# k210_V3_0.net
KiCad netlist of a schematic drawn in Altium Designer
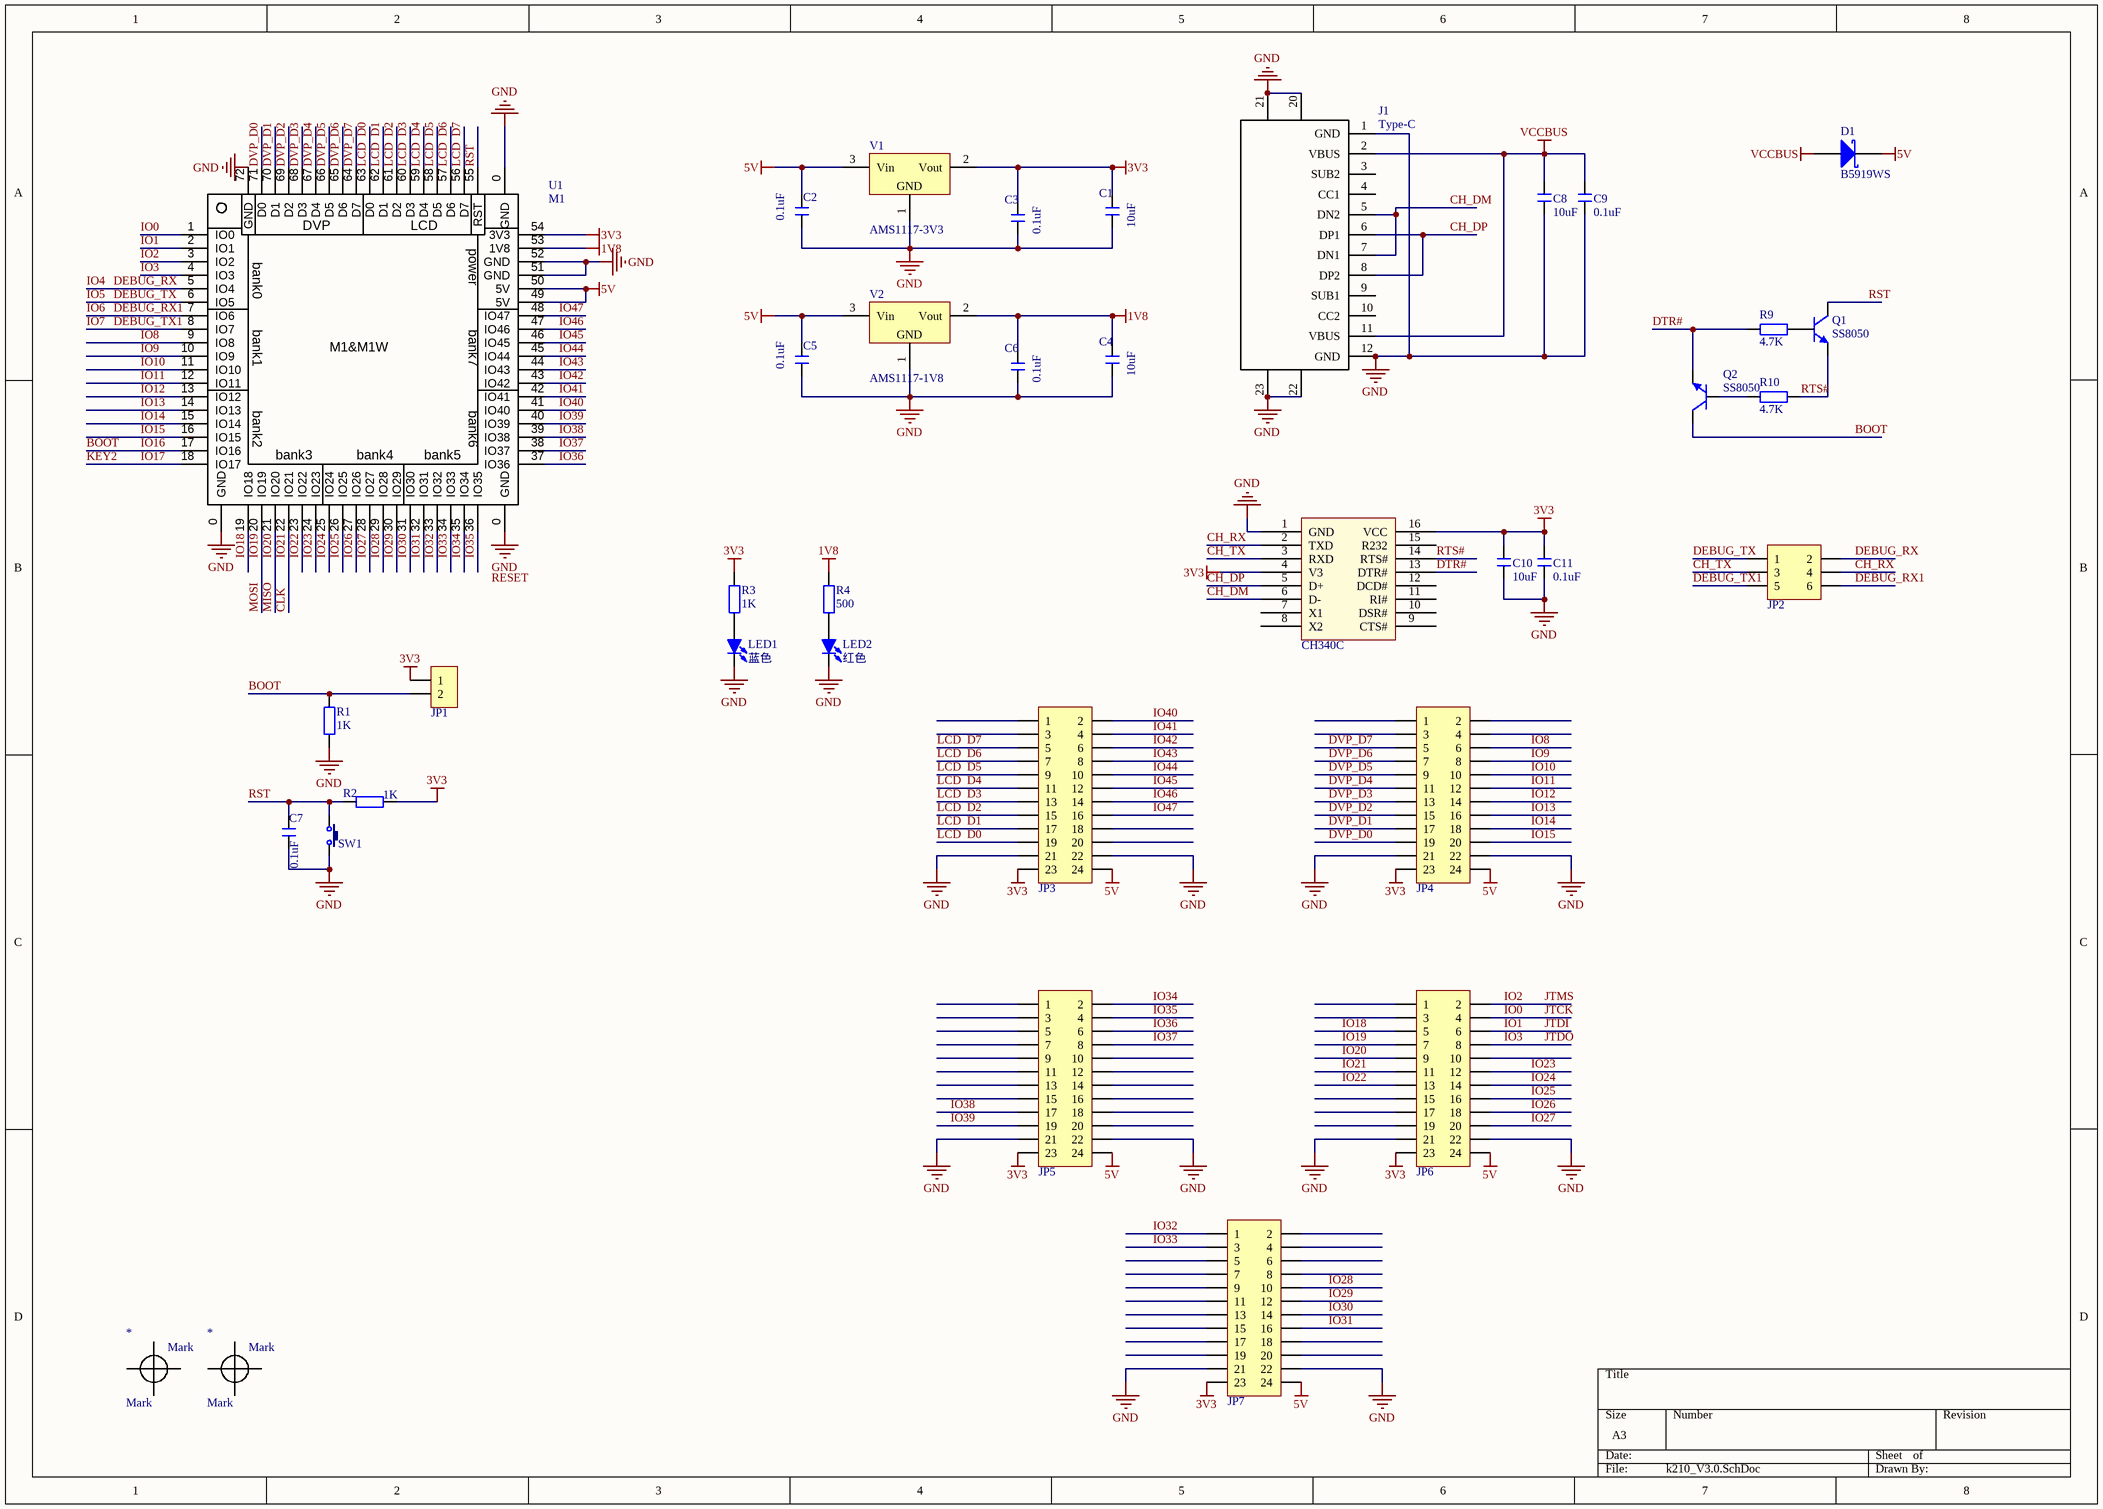
[diagram p0: k210_V3.0.SchDoc]

(export (version "E")
  (design (tool "Eeschema 10.0.6"))
  (components
    (comp (ref "C1")
      (value "10uF")
      (footprint "C 0603_L")
      (description "贴片电容")
      (libsource (lib "0.1 - 电阻-电容-电感") (part "C"))
    )
    (comp (ref "C2")
      (value "0.1uF")
      (footprint "C 0603_L")
      (description "贴片电容")
      (libsource (lib "0.1 - 电阻-电容-电感") (part "C"))
    )
    (comp (ref "C3")
      (value "0.1uF")
      (footprint "C 0603_L")
      (description "贴片电容")
      (libsource (lib "0.1 - 电阻-电容-电感") (part "C"))
    )
    (comp (ref "C4")
      (value "10uF")
      (footprint "C 0603_L")
      (description "贴片电容")
      (libsource (lib "0.1 - 电阻-电容-电感") (part "C"))
    )
    (comp (ref "C5")
      (value "0.1uF")
      (footprint "C 0603_L")
      (description "贴片电容")
      (libsource (lib "0.1 - 电阻-电容-电感") (part "C"))
    )
    (comp (ref "C6")
      (value "0.1uF")
      (footprint "C 0603_L")
      (description "贴片电容")
      (libsource (lib "0.1 - 电阻-电容-电感") (part "C"))
    )
    (comp (ref "C7")
      (value "0.1uF")
      (footprint "C 0603_L")
      (description "贴片电容")
      (libsource (lib "0.1 - 电阻-电容-电感") (part "C"))
    )
    (comp (ref "C8")
      (value "10uF")
      (footprint "C 0603_L")
      (description "贴片电容")
      (libsource (lib "0.1 - 电阻-电容-电感") (part "C"))
    )
    (comp (ref "C9")
      (value "0.1uF")
      (footprint "C 0603_L")
      (description "贴片电容")
      (libsource (lib "0.1 - 电阻-电容-电感") (part "C"))
    )
    (comp (ref "C10")
      (value "10uF")
      (footprint "C 0603_L")
      (description "贴片电容")
      (libsource (lib "0.1 - 电阻-电容-电感") (part "C"))
    )
    (comp (ref "C11")
      (value "0.1uF")
      (footprint "C 0603_L")
      (description "贴片电容")
      (libsource (lib "0.1 - 电阻-电容-电感") (part "C"))
    )
    (comp (ref "CH340C")
      (value "CH340G")
      (footprint "sop16_L")
      (libsource (lib "1.9 - CH340系列编程器芯片") (part "CH340G"))
    )
    (comp (ref "D1")
      (value "B5919WS")
      (footprint "SOD-323")
      (description "肖特基二极管")
      (libsource (lib "0.2 - 二极管-整流桥") (part "1N5819"))
    )
    (comp (ref "J1")
      (value "Type-C")
      (footprint "Type-C-16")
      (libsource (lib "TYPE-C-16PIN") (part "Type-C"))
    )
    (comp (ref "JP1")
      (value "HDR-1X2")
      (footprint "HDR2.54-M-LI-2P")
      (description "2P接插件")
      (fields (field (name "版权归属") "封装库来自淘宝 ID：黄晶宝石"))
      (libsource (lib "5.4 - 接插件-脚距2.54 (100mil) ") (part "Header 2"))
    )
    (comp (ref "JP2")
      (value "Header3X2")
      (footprint "HDR2.54-LI-2x3P")
      (description "3*2P接插件")
      (fields (field (name "版权归属") "封装库来自淘宝 ID：黄晶宝石"))
      (libsource (lib "5.4 - 接插件-脚距2.54 (100mil) ") (part "Header 3X2"))
    )
    (comp (ref "JP3")
      (value "Header 2X11")
      (footprint "HDR2.54-WI-2x12P")
      (description "12*2P接插件")
      (fields (field (name "版权归属") "封装库来自淘宝卖家 ID：黄晶宝石"))
      (libsource (lib "5.4 - 接插件-脚距2.54 (100mil) ") (part "Header 12X2"))
    )
    (comp (ref "JP4")
      (value "Header 2X11")
      (footprint "HDR2.54-WI-2x12P")
      (description "12*2P接插件")
      (fields (field (name "版权归属") "封装库来自淘宝卖家 ID：黄晶宝石"))
      (libsource (lib "5.4 - 接插件-脚距2.54 (100mil) ") (part "Header 12X2"))
    )
    (comp (ref "JP5")
      (value "Header 2X11")
      (footprint "HDR2.54-WI-2x12P")
      (description "12*2P接插件")
      (fields (field (name "版权归属") "封装库来自淘宝卖家 ID：黄晶宝石"))
      (libsource (lib "5.4 - 接插件-脚距2.54 (100mil) ") (part "Header 12X2"))
    )
    (comp (ref "JP6")
      (value "Header 2X11")
      (footprint "HDR2.54-WI-2x12P")
      (description "12*2P接插件")
      (fields (field (name "版权归属") "封装库来自淘宝卖家 ID：黄晶宝石"))
      (libsource (lib "5.4 - 接插件-脚距2.54 (100mil) ") (part "Header 12X2"))
    )
    (comp (ref "JP7")
      (value "Header 2X11")
      (footprint "HDR2.54-WI-2x12P")
      (description "12*2P接插件")
      (fields (field (name "版权归属") "封装库来自淘宝卖家 ID：黄晶宝石"))
      (libsource (lib "5.4 - 接插件-脚距2.54 (100mil) ") (part "Header 12X2"))
    )
    (comp (ref "LED1")
      (value "蓝色")
      (footprint "LED 0603R")
      (description "贴片LED")
      (fields (field (name "版权归属") "封装库来自淘宝 ID：黄晶宝石"))
      (libsource (lib "0.3 - LED发光二极管") (part "LED-SMD"))
    )
    (comp (ref "LED2")
      (value "红色")
      (footprint "LED 0603R")
      (description "贴片LED")
      (fields (field (name "版权归属") "封装库来自淘宝 ID：黄晶宝石"))
      (libsource (lib "0.3 - LED发光二极管") (part "LED-SMD"))
    )
    (comp (ref "Q1")
      (value "SS8050")
      (footprint "SOT23-3N")
      (description "高频放大-NPN型")
      (fields (field (name "版权归属") "封装库来自淘宝 ID：黄晶宝石"))
      (libsource (lib "0.4 - 三极管") (part "8050-SMD"))
    )
    (comp (ref "Q2")
      (value "SS8050")
      (footprint "SOT23-3N")
      (description "高频放大-NPN型")
      (fields (field (name "版权归属") "封装库来自淘宝 ID：黄晶宝石"))
      (libsource (lib "0.4 - 三极管") (part "8050-SMD"))
    )
    (comp (ref "R1")
      (value "1K")
      (footprint "R 0603_L")
      (description "贴片电阻")
      (libsource (lib "0.1 - 电阻-电容-电感") (part "R"))
    )
    (comp (ref "R2")
      (value "1K")
      (footprint "R 0603_L")
      (description "贴片电阻")
      (libsource (lib "0.1 - 电阻-电容-电感") (part "R"))
    )
    (comp (ref "R3")
      (value "1K")
      (footprint "R 0603_L")
      (description "贴片电阻")
      (fields (field (name "版权归属") "来自淘宝 ID：黄晶宝石"))
      (libsource (lib "0.1 - 电阻-电容-电感") (part "R"))
    )
    (comp (ref "R4")
      (value "500")
      (footprint "R 0603_L")
      (description "贴片电阻")
      (fields (field (name "版权归属") "来自淘宝 ID：黄晶宝石"))
      (libsource (lib "0.1 - 电阻-电容-电感") (part "R"))
    )
    (comp (ref "R9")
      (value "4.7K")
      (footprint "R 0603_L")
      (description "贴片电阻")
      (fields (field (name "版权归属") "来自淘宝 ID：黄晶宝石"))
      (libsource (lib "0.1 - 电阻-电容-电感") (part "R"))
    )
    (comp (ref "R10")
      (value "4.7K")
      (footprint "R 0603_L")
      (description "贴片电阻")
      (fields (field (name "版权归属") "来自淘宝 ID：黄晶宝石"))
      (libsource (lib "0.1 - 电阻-电容-电感") (part "R"))
    )
    (comp (ref "SW1")
      (value "3x6x5")
      (footprint "TSW SMD-3*6*2.5")
      (description "3x6轻触开关")
      (fields (field (name "版权归属") "封装库来自淘宝 ID：黄晶宝石"))
      (libsource (lib "0.7 - 常用按键-开关") (part "TSW 3x6"))
    )
    (comp (ref "U1") (value "M1") (footprint "M1") (libsource (lib "M1&M1W") (part "M1")))
    (comp (ref "V1")
      (value "AMS1117-3V3")
      (footprint "SOT223_L")
      (description "三端稳压芯片")
      (libsource (lib "1.1 - 电源类芯片") (part "AMS1117"))
    )
    (comp (ref "V2")
      (value "AMS1117-1V8")
      (footprint "SOT223_L")
      (description "三端稳压芯片")
      (libsource (lib "1.1 - 电源类芯片") (part "AMS1117"))
    )
  )
  (nets
    (net (code "1") (name "/BOOT") (class "Default")
      (node (ref "JP1") (pin "2") (pinfunction "2_2") (pintype "passive"))
      (node (ref "Q2") (pin "3") (pinfunction "C_3") (pintype "passive"))
      (node (ref "R1") (pin "1") (pinfunction "1_1") (pintype "passive"))
      (node (ref "U1") (pin "17") (pinfunction "IO16_17") (pintype "passive"))
    )
    (net (code "2") (name "/CH_DM") (class "Default")
      (node (ref "CH340C") (pin "6") (pinfunction "D-_6") (pintype "passive"))
      (node (ref "J1") (pin "5") (pinfunction "DN2_5") (pintype "passive"))
      (node (ref "J1") (pin "7") (pinfunction "DN1_7") (pintype "passive"))
    )
    (net (code "3") (name "/CH_DP") (class "Default")
      (node (ref "CH340C") (pin "5") (pinfunction "D+_5") (pintype "passive"))
      (node (ref "J1") (pin "6") (pinfunction "DP1_6") (pintype "passive"))
      (node (ref "J1") (pin "8") (pinfunction "DP2_8") (pintype "passive"))
    )
    (net (code "4") (name "/CH_RX") (class "Default")
      (node (ref "CH340C") (pin "2") (pinfunction "TXD_2") (pintype "passive"))
      (node (ref "JP2") (pin "4") (pinfunction "4_4") (pintype "passive"))
    )
    (net (code "5") (name "/CH_TX") (class "Default")
      (node (ref "CH340C") (pin "3") (pinfunction "RXD_3") (pintype "passive"))
      (node (ref "JP2") (pin "3") (pinfunction "3_3") (pintype "passive"))
    )
    (net (code "6") (name "/CLK") (class "Default")
      (node (ref "JP6") (pin "11") (pinfunction "11_11") (pintype "passive"))
      (node (ref "U1") (pin "22") (pinfunction "IO21_22") (pintype "passive"))
    )
    (net (code "7") (name "/DEBUG_RX") (class "Default")
      (node (ref "JP2") (pin "2") (pinfunction "2_2") (pintype "passive"))
      (node (ref "U1") (pin "5") (pinfunction "IO4_5") (pintype "passive"))
    )
    (net (code "8") (name "/DEBUG_RX1") (class "Default")
      (node (ref "JP2") (pin "6") (pinfunction "6_6") (pintype "passive"))
      (node (ref "U1") (pin "7") (pinfunction "IO6_7") (pintype "passive"))
    )
    (net (code "9") (name "/DEBUG_TX") (class "Default")
      (node (ref "JP2") (pin "1") (pinfunction "1_1") (pintype "passive"))
      (node (ref "U1") (pin "6") (pinfunction "IO5_6") (pintype "passive"))
    )
    (net (code "10") (name "/DEBUG_TX1") (class "Default")
      (node (ref "JP2") (pin "5") (pinfunction "5_5") (pintype "passive"))
      (node (ref "U1") (pin "8") (pinfunction "IO7_8") (pintype "passive"))
    )
    (net (code "11") (name "/DTR#") (class "Default")
      (node (ref "CH340C") (pin "13") (pinfunction "DTR#_13") (pintype "passive"))
      (node (ref "Q2") (pin "2") (pinfunction "E_2") (pintype "passive"))
      (node (ref "R9") (pin "1") (pinfunction "1_1") (pintype "passive"))
    )
    (net (code "12") (name "/DVP_D0") (class "Default")
      (node (ref "JP4") (pin "19") (pinfunction "19_19") (pintype "passive"))
      (node (ref "U1") (pin "71") (pinfunction "D0_71") (pintype "passive"))
    )
    (net (code "13") (name "/DVP_D1") (class "Default")
      (node (ref "JP4") (pin "17") (pinfunction "17_17") (pintype "passive"))
      (node (ref "U1") (pin "70") (pinfunction "D1_70") (pintype "passive"))
    )
    (net (code "14") (name "/DVP_D2") (class "Default")
      (node (ref "JP4") (pin "15") (pinfunction "15_15") (pintype "passive"))
      (node (ref "U1") (pin "69") (pinfunction "D2_69") (pintype "passive"))
    )
    (net (code "15") (name "/DVP_D3") (class "Default")
      (node (ref "JP4") (pin "13") (pinfunction "13_13") (pintype "passive"))
      (node (ref "U1") (pin "68") (pinfunction "D3_68") (pintype "passive"))
    )
    (net (code "16") (name "/DVP_D4") (class "Default")
      (node (ref "JP4") (pin "11") (pinfunction "11_11") (pintype "passive"))
      (node (ref "U1") (pin "67") (pinfunction "D4_67") (pintype "passive"))
    )
    (net (code "17") (name "/DVP_D5") (class "Default")
      (node (ref "JP4") (pin "9") (pinfunction "9_9") (pintype "passive"))
      (node (ref "U1") (pin "66") (pinfunction "D5_66") (pintype "passive"))
    )
    (net (code "18") (name "/DVP_D6") (class "Default")
      (node (ref "JP4") (pin "7") (pinfunction "7_7") (pintype "passive"))
      (node (ref "U1") (pin "65") (pinfunction "D6_65") (pintype "passive"))
    )
    (net (code "19") (name "/DVP_D7") (class "Default")
      (node (ref "JP4") (pin "5") (pinfunction "5_5") (pintype "passive"))
      (node (ref "U1") (pin "64") (pinfunction "D7_64") (pintype "passive"))
    )
    (net (code "20") (name "/IO0") (class "Default")
      (node (ref "JP6") (pin "4") (pinfunction "4_4") (pintype "passive"))
      (node (ref "U1") (pin "1") (pinfunction "IO0_1") (pintype "passive"))
    )
    (net (code "21") (name "/IO1") (class "Default")
      (node (ref "JP6") (pin "6") (pinfunction "6_6") (pintype "passive"))
      (node (ref "U1") (pin "2") (pinfunction "IO1_2") (pintype "passive"))
    )
    (net (code "22") (name "/IO2") (class "Default")
      (node (ref "JP6") (pin "2") (pinfunction "2_2") (pintype "passive"))
      (node (ref "U1") (pin "3") (pinfunction "IO2_3") (pintype "passive"))
    )
    (net (code "23") (name "/IO3") (class "Default")
      (node (ref "JP6") (pin "8") (pinfunction "8_8") (pintype "passive"))
      (node (ref "U1") (pin "4") (pinfunction "IO3_4") (pintype "passive"))
    )
    (net (code "24") (name "/IO8") (class "Default")
      (node (ref "JP4") (pin "6") (pinfunction "6_6") (pintype "passive"))
      (node (ref "U1") (pin "9") (pinfunction "IO8_9") (pintype "passive"))
    )
    (net (code "25") (name "/IO9") (class "Default")
      (node (ref "JP4") (pin "8") (pinfunction "8_8") (pintype "passive"))
      (node (ref "U1") (pin "10") (pinfunction "IO9_10") (pintype "passive"))
    )
    (net (code "26") (name "/IO10") (class "Default")
      (node (ref "JP4") (pin "10") (pinfunction "10_10") (pintype "passive"))
      (node (ref "U1") (pin "11") (pinfunction "IO10_11") (pintype "passive"))
    )
    (net (code "27") (name "/IO11") (class "Default")
      (node (ref "JP4") (pin "12") (pinfunction "12_12") (pintype "passive"))
      (node (ref "U1") (pin "12") (pinfunction "IO11_12") (pintype "passive"))
    )
    (net (code "28") (name "/IO12") (class "Default")
      (node (ref "JP4") (pin "14") (pinfunction "14_14") (pintype "passive"))
      (node (ref "U1") (pin "13") (pinfunction "IO12_13") (pintype "passive"))
    )
    (net (code "29") (name "/IO13") (class "Default")
      (node (ref "JP4") (pin "16") (pinfunction "16_16") (pintype "passive"))
      (node (ref "U1") (pin "14") (pinfunction "IO13_14") (pintype "passive"))
    )
    (net (code "30") (name "/IO14") (class "Default")
      (node (ref "JP4") (pin "18") (pinfunction "18_18") (pintype "passive"))
      (node (ref "U1") (pin "15") (pinfunction "IO14_15") (pintype "passive"))
    )
    (net (code "31") (name "/IO15") (class "Default")
      (node (ref "JP4") (pin "20") (pinfunction "20_20") (pintype "passive"))
      (node (ref "U1") (pin "16") (pinfunction "IO15_16") (pintype "passive"))
    )
    (net (code "32") (name "/IO17") (class "Default")
      (node (ref "U1") (pin "18") (pinfunction "IO17_18") (pintype "passive"))
    )
    (net (code "33") (name "/IO18") (class "Default")
      (node (ref "JP6") (pin "5") (pinfunction "5_5") (pintype "passive"))
      (node (ref "U1") (pin "19") (pinfunction "IO18_19") (pintype "passive"))
    )
    (net (code "34") (name "/IO19") (class "Default")
      (node (ref "JP6") (pin "7") (pinfunction "7_7") (pintype "passive"))
      (node (ref "U1") (pin "20") (pinfunction "IO19_20") (pintype "passive"))
    )
    (net (code "35") (name "/IO20") (class "Default")
      (node (ref "JP6") (pin "9") (pinfunction "9_9") (pintype "passive"))
      (node (ref "U1") (pin "21") (pinfunction "IO20_21") (pintype "passive"))
    )
    (net (code "36") (name "/IO22") (class "Default")
      (node (ref "JP6") (pin "13") (pinfunction "13_13") (pintype "passive"))
      (node (ref "U1") (pin "23") (pinfunction "IO22_23") (pintype "passive"))
    )
    (net (code "37") (name "/IO23") (class "Default")
      (node (ref "JP6") (pin "12") (pinfunction "12_12") (pintype "passive"))
      (node (ref "U1") (pin "24") (pinfunction "IO23_24") (pintype "passive"))
    )
    (net (code "38") (name "/IO24") (class "Default")
      (node (ref "JP6") (pin "14") (pinfunction "14_14") (pintype "passive"))
      (node (ref "U1") (pin "25") (pinfunction "IO24_25") (pintype "passive"))
    )
    (net (code "39") (name "/IO25") (class "Default")
      (node (ref "JP6") (pin "16") (pinfunction "16_16") (pintype "passive"))
      (node (ref "U1") (pin "26") (pinfunction "IO25_26") (pintype "passive"))
    )
    (net (code "40") (name "/IO26") (class "Default")
      (node (ref "JP6") (pin "18") (pinfunction "18_18") (pintype "passive"))
      (node (ref "U1") (pin "27") (pinfunction "IO26_27") (pintype "passive"))
    )
    (net (code "41") (name "/IO27") (class "Default")
      (node (ref "JP6") (pin "20") (pinfunction "20_20") (pintype "passive"))
      (node (ref "U1") (pin "28") (pinfunction "IO27_28") (pintype "passive"))
    )
    (net (code "42") (name "/IO28") (class "Default")
      (node (ref "JP7") (pin "10") (pinfunction "10_10") (pintype "passive"))
      (node (ref "U1") (pin "29") (pinfunction "IO28_29") (pintype "passive"))
    )
    (net (code "43") (name "/IO29") (class "Default")
      (node (ref "JP7") (pin "12") (pinfunction "12_12") (pintype "passive"))
      (node (ref "U1") (pin "30") (pinfunction "IO29_30") (pintype "passive"))
    )
    (net (code "44") (name "/IO30") (class "Default")
      (node (ref "JP7") (pin "14") (pinfunction "14_14") (pintype "passive"))
      (node (ref "U1") (pin "31") (pinfunction "IO30_31") (pintype "passive"))
    )
    (net (code "45") (name "/IO31") (class "Default")
      (node (ref "JP7") (pin "16") (pinfunction "16_16") (pintype "passive"))
      (node (ref "U1") (pin "32") (pinfunction "IO31_32") (pintype "passive"))
    )
    (net (code "46") (name "/IO32") (class "Default")
      (node (ref "JP7") (pin "1") (pinfunction "1_1") (pintype "passive"))
      (node (ref "U1") (pin "33") (pinfunction "IO32_33") (pintype "passive"))
    )
    (net (code "47") (name "/IO33") (class "Default")
      (node (ref "JP7") (pin "3") (pinfunction "3_3") (pintype "passive"))
      (node (ref "U1") (pin "34") (pinfunction "IO33_34") (pintype "passive"))
    )
    (net (code "48") (name "/IO34") (class "Default")
      (node (ref "JP5") (pin "2") (pinfunction "2_2") (pintype "passive"))
      (node (ref "U1") (pin "35") (pinfunction "IO34_35") (pintype "passive"))
    )
    (net (code "49") (name "/IO35") (class "Default")
      (node (ref "JP5") (pin "4") (pinfunction "4_4") (pintype "passive"))
      (node (ref "U1") (pin "36") (pinfunction "IO35_36") (pintype "passive"))
    )
    (net (code "50") (name "/IO36") (class "Default")
      (node (ref "JP5") (pin "6") (pinfunction "6_6") (pintype "passive"))
      (node (ref "U1") (pin "37") (pinfunction "IO36_37") (pintype "passive"))
    )
    (net (code "51") (name "/IO37") (class "Default")
      (node (ref "JP5") (pin "8") (pinfunction "8_8") (pintype "passive"))
      (node (ref "U1") (pin "38") (pinfunction "IO37_38") (pintype "passive"))
    )
    (net (code "52") (name "/IO38") (class "Default")
      (node (ref "JP5") (pin "17") (pinfunction "17_17") (pintype "passive"))
      (node (ref "U1") (pin "39") (pinfunction "IO38_39") (pintype "passive"))
    )
    (net (code "53") (name "/IO39") (class "Default")
      (node (ref "JP5") (pin "19") (pinfunction "19_19") (pintype "passive"))
      (node (ref "U1") (pin "40") (pinfunction "IO39_40") (pintype "passive"))
    )
    (net (code "54") (name "/IO40") (class "Default")
      (node (ref "JP3") (pin "2") (pinfunction "2_2") (pintype "passive"))
      (node (ref "U1") (pin "41") (pinfunction "IO40_41") (pintype "passive"))
    )
    (net (code "55") (name "/IO41") (class "Default")
      (node (ref "JP3") (pin "4") (pinfunction "4_4") (pintype "passive"))
      (node (ref "U1") (pin "42") (pinfunction "IO41_42") (pintype "passive"))
    )
    (net (code "56") (name "/IO42") (class "Default")
      (node (ref "JP3") (pin "6") (pinfunction "6_6") (pintype "passive"))
      (node (ref "U1") (pin "43") (pinfunction "IO42_43") (pintype "passive"))
    )
    (net (code "57") (name "/IO43") (class "Default")
      (node (ref "JP3") (pin "8") (pinfunction "8_8") (pintype "passive"))
      (node (ref "U1") (pin "44") (pinfunction "IO43_44") (pintype "passive"))
    )
    (net (code "58") (name "/IO44") (class "Default")
      (node (ref "JP3") (pin "10") (pinfunction "10_10") (pintype "passive"))
      (node (ref "U1") (pin "45") (pinfunction "IO44_45") (pintype "passive"))
    )
    (net (code "59") (name "/IO45") (class "Default")
      (node (ref "JP3") (pin "12") (pinfunction "12_12") (pintype "passive"))
      (node (ref "U1") (pin "46") (pinfunction "IO45_46") (pintype "passive"))
    )
    (net (code "60") (name "/IO46") (class "Default")
      (node (ref "JP3") (pin "14") (pinfunction "14_14") (pintype "passive"))
      (node (ref "U1") (pin "47") (pinfunction "IO46_47") (pintype "passive"))
    )
    (net (code "61") (name "/IO47") (class "Default")
      (node (ref "JP3") (pin "16") (pinfunction "16_16") (pintype "passive"))
      (node (ref "U1") (pin "48") (pinfunction "IO47_48") (pintype "passive"))
    )
    (net (code "62") (name "/LCD  D0") (class "Default")
      (node (ref "JP3") (pin "19") (pinfunction "19_19") (pintype "passive"))
      (node (ref "U1") (pin "63") (pinfunction "D0_63") (pintype "passive"))
    )
    (net (code "63") (name "/LCD  D1") (class "Default")
      (node (ref "JP3") (pin "17") (pinfunction "17_17") (pintype "passive"))
      (node (ref "U1") (pin "62") (pinfunction "D1_62") (pintype "passive"))
    )
    (net (code "64") (name "/LCD  D2") (class "Default")
      (node (ref "JP3") (pin "15") (pinfunction "15_15") (pintype "passive"))
      (node (ref "U1") (pin "61") (pinfunction "D2_61") (pintype "passive"))
    )
    (net (code "65") (name "/LCD  D3") (class "Default")
      (node (ref "JP3") (pin "13") (pinfunction "13_13") (pintype "passive"))
      (node (ref "U1") (pin "60") (pinfunction "D3_60") (pintype "passive"))
    )
    (net (code "66") (name "/LCD  D4") (class "Default")
      (node (ref "JP3") (pin "11") (pinfunction "11_11") (pintype "passive"))
      (node (ref "U1") (pin "59") (pinfunction "D4_59") (pintype "passive"))
    )
    (net (code "67") (name "/LCD  D5") (class "Default")
      (node (ref "JP3") (pin "9") (pinfunction "9_9") (pintype "passive"))
      (node (ref "U1") (pin "58") (pinfunction "D5_58") (pintype "passive"))
    )
    (net (code "68") (name "/LCD  D6") (class "Default")
      (node (ref "JP3") (pin "7") (pinfunction "7_7") (pintype "passive"))
      (node (ref "U1") (pin "57") (pinfunction "D6_57") (pintype "passive"))
    )
    (net (code "69") (name "/LCD  D7") (class "Default")
      (node (ref "JP3") (pin "5") (pinfunction "5_5") (pintype "passive"))
      (node (ref "U1") (pin "56") (pinfunction "D7_56") (pintype "passive"))
    )
    (net (code "71") (name "/RST") (class "Default")
      (node (ref "C7") (pin "2") (pinfunction "2_2") (pintype "passive"))
      (node (ref "Q1") (pin "3") (pinfunction "C_3") (pintype "passive"))
      (node (ref "R2") (pin "2") (pinfunction "2_2") (pintype "passive"))
      (node (ref "SW1") (pin "1") (pinfunction "1_1") (pintype "passive"))
      (node (ref "U1") (pin "55") (pinfunction "RST_55") (pintype "passive"))
    )
    (net (code "72") (name "/RTS#") (class "Default")
      (node (ref "CH340C") (pin "14") (pinfunction "RTS#_14") (pintype "passive"))
      (node (ref "Q1") (pin "2") (pinfunction "E_2") (pintype "passive"))
      (node (ref "R10") (pin "2") (pinfunction "2_2") (pintype "passive"))
    )
    (net (code "73") (name "1V8") (class "Default")
      (node (ref "C4") (pin "2") (pinfunction "2_2") (pintype "passive"))
      (node (ref "C6") (pin "2") (pinfunction "2_2") (pintype "passive"))
      (node (ref "R4") (pin "2") (pinfunction "2_2") (pintype "passive"))
      (node (ref "U1") (pin "53") (pinfunction "1V8_53") (pintype "passive"))
      (node (ref "V2") (pin "2") (pinfunction "Vout_2") (pintype "passive"))
    )
    (net (code "74") (name "3V3") (class "Default")
      (node (ref "C1") (pin "2") (pinfunction "2_2") (pintype "passive"))
      (node (ref "C10") (pin "2") (pinfunction "2_2") (pintype "passive"))
      (node (ref "C11") (pin "2") (pinfunction "2_2") (pintype "passive"))
      (node (ref "C3") (pin "2") (pinfunction "2_2") (pintype "passive"))
      (node (ref "CH340C") (pin "16") (pinfunction "VCC_16") (pintype "passive"))
      (node (ref "CH340C") (pin "4") (pinfunction "V3_4") (pintype "passive"))
      (node (ref "JP1") (pin "1") (pinfunction "1_1") (pintype "passive"))
      (node (ref "JP3") (pin "23") (pinfunction "23_23") (pintype "passive"))
      (node (ref "JP4") (pin "23") (pinfunction "23_23") (pintype "passive"))
      (node (ref "JP5") (pin "23") (pinfunction "23_23") (pintype "passive"))
      (node (ref "JP6") (pin "23") (pinfunction "23_23") (pintype "passive"))
      (node (ref "JP7") (pin "23") (pinfunction "23_23") (pintype "passive"))
      (node (ref "R2") (pin "1") (pinfunction "1_1") (pintype "passive"))
      (node (ref "R3") (pin "2") (pinfunction "2_2") (pintype "passive"))
      (node (ref "U1") (pin "54") (pinfunction "3V3_54") (pintype "passive"))
      (node (ref "V1") (pin "2") (pinfunction "Vout_2") (pintype "passive"))
    )
    (net (code "75") (name "5V") (class "Default")
      (node (ref "C2") (pin "2") (pinfunction "2_2") (pintype "passive"))
      (node (ref "C5") (pin "2") (pinfunction "2_2") (pintype "passive"))
      (node (ref "D1") (pin "2") (pinfunction "K_2") (pintype "passive"))
      (node (ref "JP3") (pin "24") (pinfunction "24_24") (pintype "passive"))
      (node (ref "JP4") (pin "24") (pinfunction "24_24") (pintype "passive"))
      (node (ref "JP5") (pin "24") (pinfunction "24_24") (pintype "passive"))
      (node (ref "JP6") (pin "24") (pinfunction "24_24") (pintype "passive"))
      (node (ref "JP7") (pin "24") (pinfunction "24_24") (pintype "passive"))
      (node (ref "U1") (pin "49") (pinfunction "5V_49") (pintype "passive"))
      (node (ref "U1") (pin "50") (pinfunction "5V_50") (pintype "passive"))
      (node (ref "V1") (pin "3") (pinfunction "Vin_3") (pintype "passive"))
      (node (ref "V2") (pin "3") (pinfunction "Vin_3") (pintype "passive"))
    )
    (net (code "76") (name "GND") (class "Default")
      (node (ref "C1") (pin "1") (pinfunction "1_1") (pintype "passive"))
      (node (ref "C10") (pin "1") (pinfunction "1_1") (pintype "passive"))
      (node (ref "C11") (pin "1") (pinfunction "1_1") (pintype "passive"))
      (node (ref "C2") (pin "1") (pinfunction "1_1") (pintype "passive"))
      (node (ref "C3") (pin "1") (pinfunction "1_1") (pintype "passive"))
      (node (ref "C4") (pin "1") (pinfunction "1_1") (pintype "passive"))
      (node (ref "C5") (pin "1") (pinfunction "1_1") (pintype "passive"))
      (node (ref "C6") (pin "1") (pinfunction "1_1") (pintype "passive"))
      (node (ref "C7") (pin "1") (pinfunction "1_1") (pintype "passive"))
      (node (ref "C8") (pin "1") (pinfunction "1_1") (pintype "passive"))
      (node (ref "C9") (pin "1") (pinfunction "1_1") (pintype "passive"))
      (node (ref "CH340C") (pin "1") (pinfunction "GND_1") (pintype "passive"))
      (node (ref "J1") (pin "1") (pinfunction "GND_1") (pintype "passive"))
      (node (ref "J1") (pin "12") (pinfunction "GND_12") (pintype "passive"))
      (node (ref "J1") (pin "20") (pintype "passive"))
      (node (ref "J1") (pin "21") (pintype "passive"))
      (node (ref "J1") (pin "22") (pintype "passive"))
      (node (ref "J1") (pin "23") (pintype "passive"))
      (node (ref "JP3") (pin "21") (pinfunction "21_21") (pintype "passive"))
      (node (ref "JP3") (pin "22") (pinfunction "22_22") (pintype "passive"))
      (node (ref "JP4") (pin "21") (pinfunction "21_21") (pintype "passive"))
      (node (ref "JP4") (pin "22") (pinfunction "22_22") (pintype "passive"))
      (node (ref "JP5") (pin "21") (pinfunction "21_21") (pintype "passive"))
      (node (ref "JP5") (pin "22") (pinfunction "22_22") (pintype "passive"))
      (node (ref "JP6") (pin "21") (pinfunction "21_21") (pintype "passive"))
      (node (ref "JP6") (pin "22") (pinfunction "22_22") (pintype "passive"))
      (node (ref "JP7") (pin "21") (pinfunction "21_21") (pintype "passive"))
      (node (ref "JP7") (pin "22") (pinfunction "22_22") (pintype "passive"))
      (node (ref "LED1") (pin "2") (pinfunction "K_2") (pintype "passive"))
      (node (ref "LED2") (pin "2") (pinfunction "K_2") (pintype "passive"))
      (node (ref "R1") (pin "2") (pinfunction "2_2") (pintype "passive"))
      (node (ref "SW1") (pin "2") (pinfunction "2_2") (pintype "passive"))
      (node (ref "U1") (pin "0") (pinfunction "GND_0") (pintype "passive"))
      (node (ref "U1") (pin "51") (pinfunction "GND_51") (pintype "passive"))
      (node (ref "U1") (pin "52") (pinfunction "GND_52") (pintype "passive"))
      (node (ref "U1") (pin "72") (pinfunction "GND_72") (pintype "passive"))
      (node (ref "V1") (pin "1") (pinfunction "GND_1") (pintype "passive"))
      (node (ref "V2") (pin "1") (pinfunction "GND_1") (pintype "passive"))
    )
    (net (code "77") (name "Net-(LED1-A)") (class "Default")
      (node (ref "LED1") (pin "1") (pinfunction "A_1") (pintype "passive"))
      (node (ref "R3") (pin "1") (pinfunction "1_1") (pintype "passive"))
    )
    (net (code "78") (name "Net-(LED2-A)") (class "Default")
      (node (ref "LED2") (pin "1") (pinfunction "A_1") (pintype "passive"))
      (node (ref "R4") (pin "1") (pinfunction "1_1") (pintype "passive"))
    )
    (net (code "79") (name "Net-(Q1-B)") (class "Default")
      (node (ref "Q1") (pin "1") (pinfunction "B_1") (pintype "passive"))
      (node (ref "R9") (pin "2") (pinfunction "2_2") (pintype "passive"))
    )
    (net (code "80") (name "Net-(Q2-B)") (class "Default")
      (node (ref "Q2") (pin "1") (pinfunction "B_1") (pintype "passive"))
      (node (ref "R10") (pin "1") (pinfunction "1_1") (pintype "passive"))
    )
    (net (code "81") (name "VCCBUS") (class "Default")
      (node (ref "C8") (pin "2") (pinfunction "2_2") (pintype "passive"))
      (node (ref "C9") (pin "2") (pinfunction "2_2") (pintype "passive"))
      (node (ref "D1") (pin "1") (pinfunction "A_1") (pintype "passive"))
      (node (ref "J1") (pin "11") (pinfunction "VBUS_11") (pintype "passive"))
      (node (ref "J1") (pin "2") (pinfunction "VBUS_2") (pintype "passive"))
    )
    (net (code "82") (name "unconnected-(CH340C-CTS#-Pad9)") (class "Default")
      (node (ref "CH340C") (pin "9") (pinfunction "CTS#_9") (pintype "passive"))
    )
    (net (code "83") (name "unconnected-(CH340C-DCD#-Pad12)") (class "Default")
      (node (ref "CH340C") (pin "12") (pinfunction "DCD#_12") (pintype "passive"))
    )
    (net (code "84") (name "unconnected-(CH340C-DSR#-Pad10)") (class "Default")
      (node (ref "CH340C") (pin "10") (pinfunction "DSR#_10") (pintype "passive"))
    )
    (net (code "85") (name "unconnected-(CH340C-R232-Pad15)") (class "Default")
      (node (ref "CH340C") (pin "15") (pinfunction "R232_15") (pintype "passive"))
    )
    (net (code "86") (name "unconnected-(CH340C-RI#-Pad11)") (class "Default")
      (node (ref "CH340C") (pin "11") (pinfunction "RI#_11") (pintype "passive"))
    )
    (net (code "87") (name "unconnected-(CH340C-X1-Pad7)") (class "Default")
      (node (ref "CH340C") (pin "7") (pinfunction "X1_7") (pintype "passive"))
    )
    (net (code "88") (name "unconnected-(CH340C-X2-Pad8)") (class "Default")
      (node (ref "CH340C") (pin "8") (pinfunction "X2_8") (pintype "passive"))
    )
    (net (code "89") (name "unconnected-(J1-CC1-Pad4)") (class "Default")
      (node (ref "J1") (pin "4") (pinfunction "CC1_4") (pintype "passive"))
    )
    (net (code "90") (name "unconnected-(J1-CC2-Pad10)") (class "Default")
      (node (ref "J1") (pin "10") (pinfunction "CC2_10") (pintype "passive"))
    )
    (net (code "91") (name "unconnected-(J1-SUB1-Pad9)") (class "Default")
      (node (ref "J1") (pin "9") (pinfunction "SUB1_9") (pintype "passive"))
    )
    (net (code "92") (name "unconnected-(J1-SUB2-Pad3)") (class "Default")
      (node (ref "J1") (pin "3") (pinfunction "SUB2_3") (pintype "passive"))
    )
    (net (code "93") (name "unconnected-(JP3-Pad1)") (class "Default")
      (node (ref "JP3") (pin "1") (pinfunction "1_1") (pintype "passive"))
    )
    (net (code "94") (name "unconnected-(JP3-Pad3)") (class "Default")
      (node (ref "JP3") (pin "3") (pinfunction "3_3") (pintype "passive"))
    )
    (net (code "95") (name "unconnected-(JP3-Pad18)") (class "Default")
      (node (ref "JP3") (pin "18") (pinfunction "18_18") (pintype "passive"))
    )
    (net (code "96") (name "unconnected-(JP3-Pad20)") (class "Default")
      (node (ref "JP3") (pin "20") (pinfunction "20_20") (pintype "passive"))
    )
    (net (code "97") (name "unconnected-(JP4-Pad1)") (class "Default")
      (node (ref "JP4") (pin "1") (pinfunction "1_1") (pintype "passive"))
    )
    (net (code "98") (name "unconnected-(JP4-Pad2)") (class "Default")
      (node (ref "JP4") (pin "2") (pinfunction "2_2") (pintype "passive"))
    )
    (net (code "99") (name "unconnected-(JP4-Pad3)") (class "Default")
      (node (ref "JP4") (pin "3") (pinfunction "3_3") (pintype "passive"))
    )
    (net (code "100") (name "unconnected-(JP4-Pad4)") (class "Default")
      (node (ref "JP4") (pin "4") (pinfunction "4_4") (pintype "passive"))
    )
    (net (code "101") (name "unconnected-(JP5-Pad1)") (class "Default")
      (node (ref "JP5") (pin "1") (pinfunction "1_1") (pintype "passive"))
    )
    (net (code "102") (name "unconnected-(JP5-Pad3)") (class "Default")
      (node (ref "JP5") (pin "3") (pinfunction "3_3") (pintype "passive"))
    )
    (net (code "103") (name "unconnected-(JP5-Pad5)") (class "Default")
      (node (ref "JP5") (pin "5") (pinfunction "5_5") (pintype "passive"))
    )
    (net (code "104") (name "unconnected-(JP5-Pad7)") (class "Default")
      (node (ref "JP5") (pin "7") (pinfunction "7_7") (pintype "passive"))
    )
    (net (code "105") (name "unconnected-(JP5-Pad9)") (class "Default")
      (node (ref "JP5") (pin "9") (pinfunction "9_9") (pintype "passive"))
    )
    (net (code "106") (name "unconnected-(JP5-Pad10)") (class "Default")
      (node (ref "JP5") (pin "10") (pinfunction "10_10") (pintype "passive"))
    )
    (net (code "107") (name "unconnected-(JP5-Pad11)") (class "Default")
      (node (ref "JP5") (pin "11") (pinfunction "11_11") (pintype "passive"))
    )
    (net (code "108") (name "unconnected-(JP5-Pad12)") (class "Default")
      (node (ref "JP5") (pin "12") (pinfunction "12_12") (pintype "passive"))
    )
    (net (code "109") (name "unconnected-(JP5-Pad13)") (class "Default")
      (node (ref "JP5") (pin "13") (pinfunction "13_13") (pintype "passive"))
    )
    (net (code "110") (name "unconnected-(JP5-Pad14)") (class "Default")
      (node (ref "JP5") (pin "14") (pinfunction "14_14") (pintype "passive"))
    )
    (net (code "111") (name "unconnected-(JP5-Pad15)") (class "Default")
      (node (ref "JP5") (pin "15") (pinfunction "15_15") (pintype "passive"))
    )
    (net (code "112") (name "unconnected-(JP5-Pad16)") (class "Default")
      (node (ref "JP5") (pin "16") (pinfunction "16_16") (pintype "passive"))
    )
    (net (code "113") (name "unconnected-(JP5-Pad18)") (class "Default")
      (node (ref "JP5") (pin "18") (pinfunction "18_18") (pintype "passive"))
    )
    (net (code "114") (name "unconnected-(JP5-Pad20)") (class "Default")
      (node (ref "JP5") (pin "20") (pinfunction "20_20") (pintype "passive"))
    )
    (net (code "115") (name "unconnected-(JP6-Pad1)") (class "Default")
      (node (ref "JP6") (pin "1") (pinfunction "1_1") (pintype "passive"))
    )
    (net (code "116") (name "unconnected-(JP6-Pad3)") (class "Default")
      (node (ref "JP6") (pin "3") (pinfunction "3_3") (pintype "passive"))
    )
    (net (code "117") (name "unconnected-(JP6-Pad10)") (class "Default")
      (node (ref "JP6") (pin "10") (pinfunction "10_10") (pintype "passive"))
    )
    (net (code "118") (name "unconnected-(JP6-Pad15)") (class "Default")
      (node (ref "JP6") (pin "15") (pinfunction "15_15") (pintype "passive"))
    )
    (net (code "119") (name "unconnected-(JP6-Pad17)") (class "Default")
      (node (ref "JP6") (pin "17") (pinfunction "17_17") (pintype "passive"))
    )
    (net (code "120") (name "unconnected-(JP6-Pad19)") (class "Default")
      (node (ref "JP6") (pin "19") (pinfunction "19_19") (pintype "passive"))
    )
    (net (code "121") (name "unconnected-(JP7-Pad2)") (class "Default")
      (node (ref "JP7") (pin "2") (pinfunction "2_2") (pintype "passive"))
    )
    (net (code "122") (name "unconnected-(JP7-Pad4)") (class "Default")
      (node (ref "JP7") (pin "4") (pinfunction "4_4") (pintype "passive"))
    )
    (net (code "123") (name "unconnected-(JP7-Pad5)") (class "Default")
      (node (ref "JP7") (pin "5") (pinfunction "5_5") (pintype "passive"))
    )
    (net (code "124") (name "unconnected-(JP7-Pad6)") (class "Default")
      (node (ref "JP7") (pin "6") (pinfunction "6_6") (pintype "passive"))
    )
    (net (code "125") (name "unconnected-(JP7-Pad7)") (class "Default")
      (node (ref "JP7") (pin "7") (pinfunction "7_7") (pintype "passive"))
    )
    (net (code "126") (name "unconnected-(JP7-Pad8)") (class "Default")
      (node (ref "JP7") (pin "8") (pinfunction "8_8") (pintype "passive"))
    )
    (net (code "127") (name "unconnected-(JP7-Pad9)") (class "Default")
      (node (ref "JP7") (pin "9") (pinfunction "9_9") (pintype "passive"))
    )
    (net (code "128") (name "unconnected-(JP7-Pad11)") (class "Default")
      (node (ref "JP7") (pin "11") (pinfunction "11_11") (pintype "passive"))
    )
    (net (code "129") (name "unconnected-(JP7-Pad13)") (class "Default")
      (node (ref "JP7") (pin "13") (pinfunction "13_13") (pintype "passive"))
    )
    (net (code "130") (name "unconnected-(JP7-Pad15)") (class "Default")
      (node (ref "JP7") (pin "15") (pinfunction "15_15") (pintype "passive"))
    )
    (net (code "131") (name "unconnected-(JP7-Pad17)") (class "Default")
      (node (ref "JP7") (pin "17") (pinfunction "17_17") (pintype "passive"))
    )
    (net (code "132") (name "unconnected-(JP7-Pad18)") (class "Default")
      (node (ref "JP7") (pin "18") (pinfunction "18_18") (pintype "passive"))
    )
    (net (code "133") (name "unconnected-(JP7-Pad19)") (class "Default")
      (node (ref "JP7") (pin "19") (pinfunction "19_19") (pintype "passive"))
    )
    (net (code "134") (name "unconnected-(JP7-Pad20)") (class "Default")
      (node (ref "JP7") (pin "20") (pinfunction "20_20") (pintype "passive"))
    )
  )
)
